# Power.net
KiCad netlist of a schematic drawn in Altium Designer
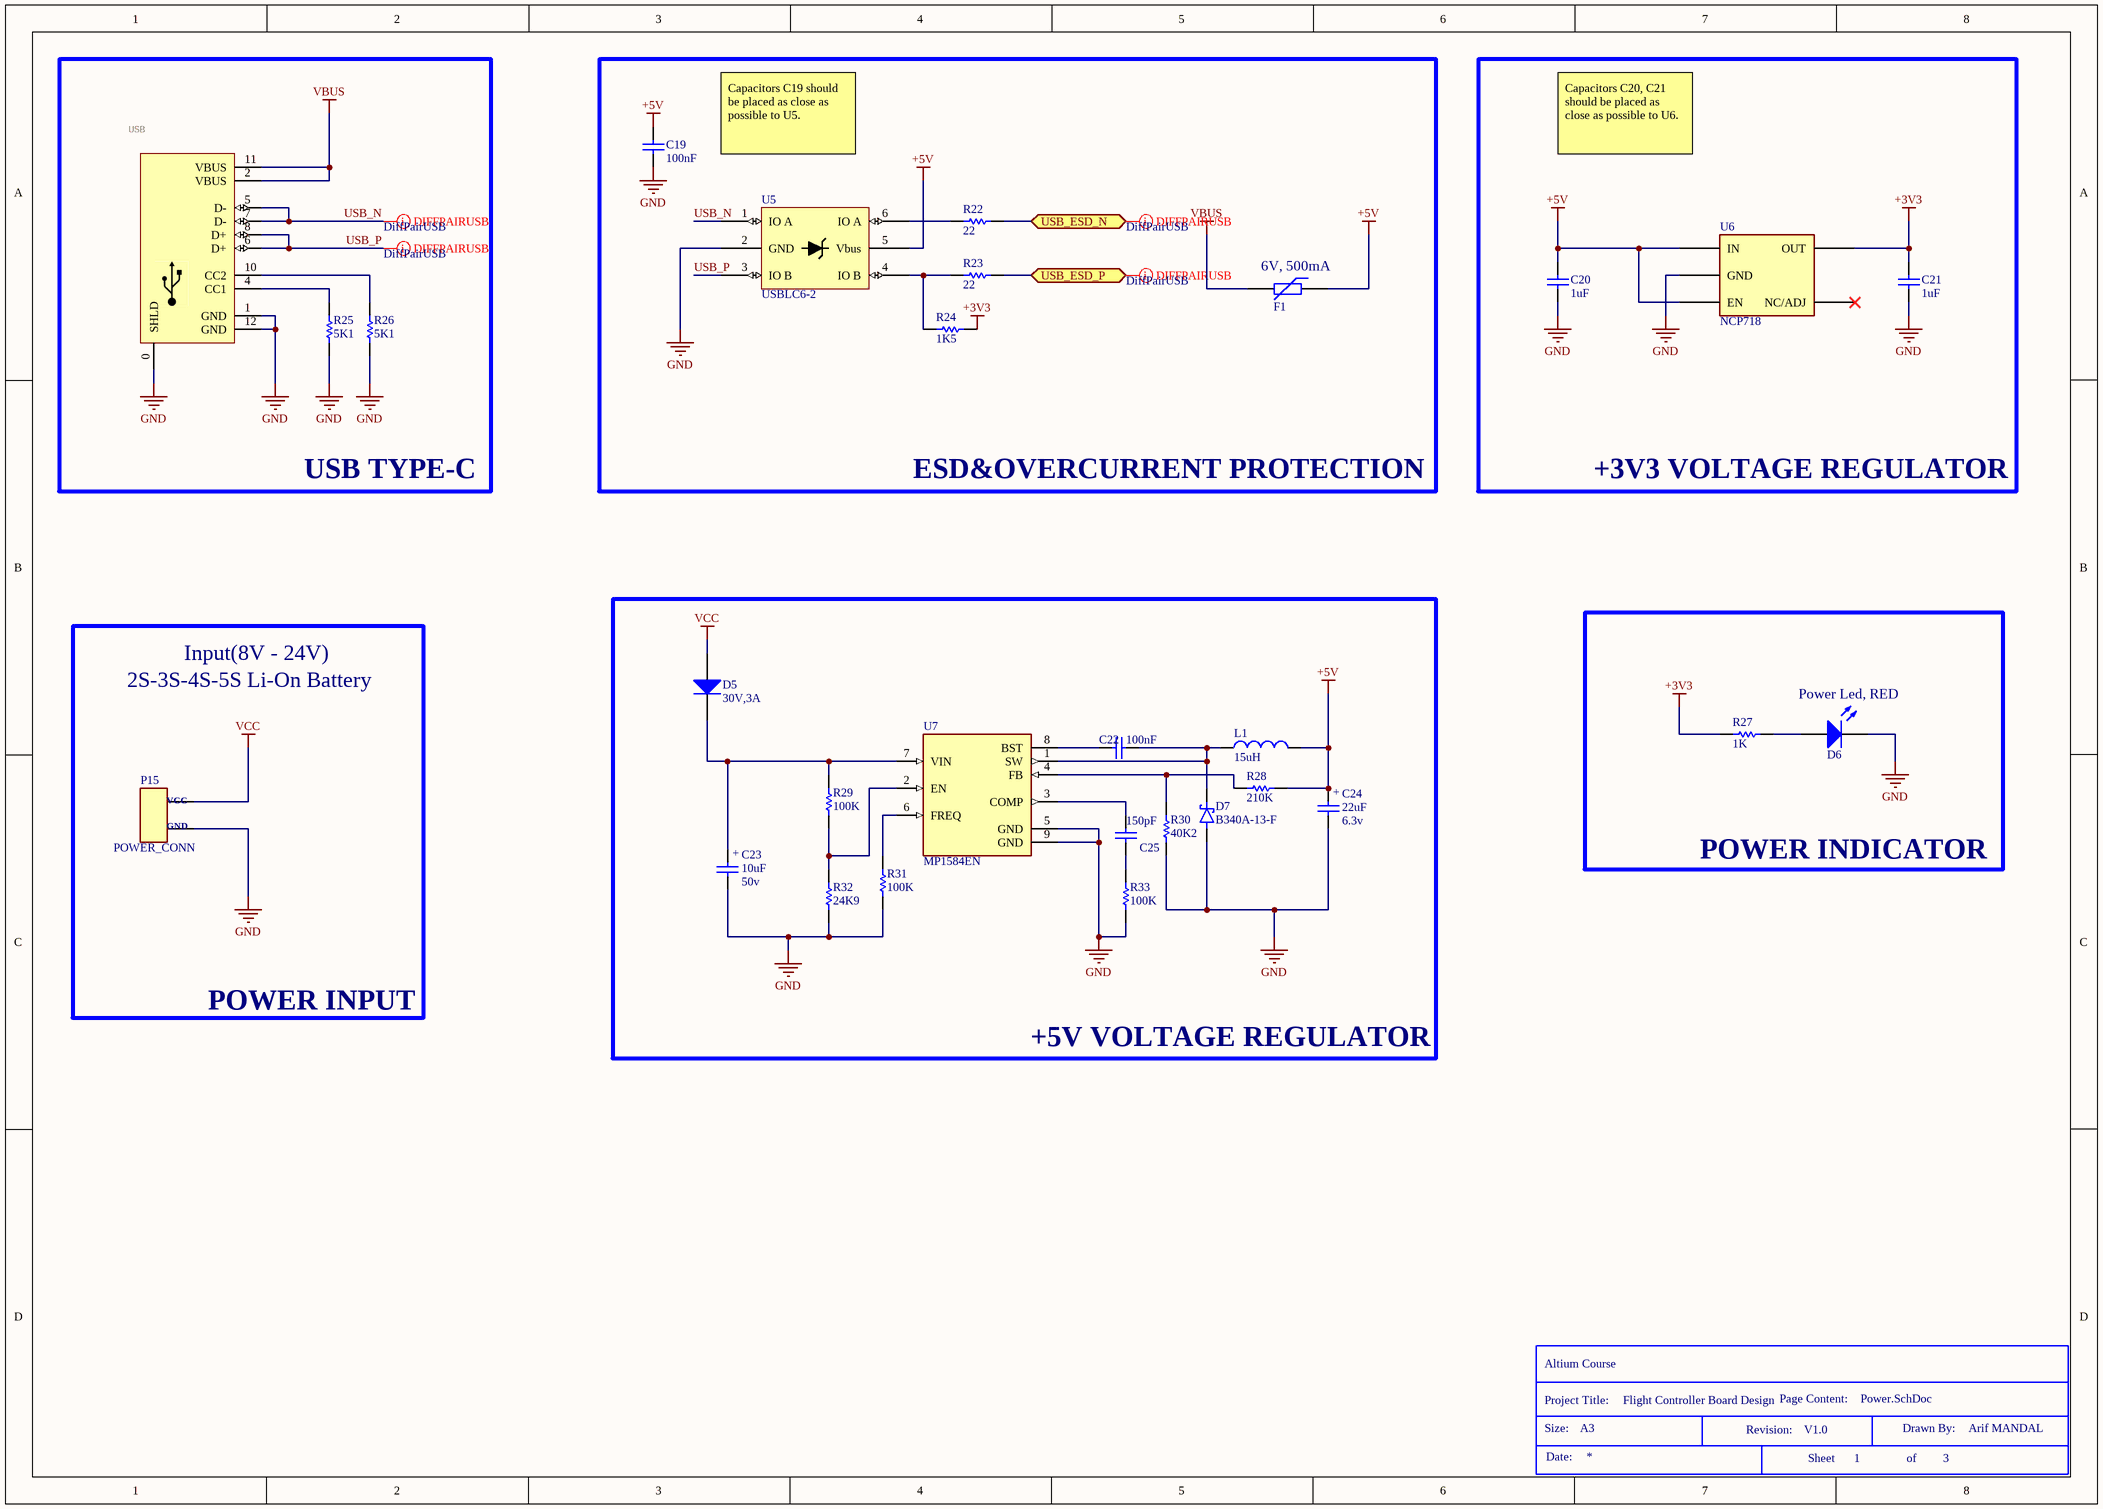
[diagram p0: Power.SchDoc]

(export (version "E")
  (design (tool "Eeschema 10.0.6"))
  (components
    (comp (ref "*")
      (value "Title Block")
      (fields (field (name "SIZE") "A3") (field (name "DRAWN BY") "Arif MANDAL"))
      (libsource (lib "Flight_Controller_Board_Design") (part "Title Block"))
    )
    (comp (ref "C19")
      (value "100nF")
      (footprint "C805")
      (description "Capacitor")
      (fields (field (name "DESIGNER") "Parsa Malekpour"))
      (libsource (lib "ParsaLibrary") (part "Cap"))
    )
    (comp (ref "C20")
      (value "1uF")
      (footprint "C805")
      (description "Capacitor")
      (fields (field (name "DESIGNER") "Parsa Malekpour"))
      (libsource (lib "ParsaLibrary") (part "Cap"))
    )
    (comp (ref "C21")
      (value "1uF")
      (footprint "C805")
      (description "Capacitor")
      (fields (field (name "DESIGNER") "Parsa Malekpour"))
      (libsource (lib "ParsaLibrary") (part "Cap"))
    )
    (comp (ref "C22")
      (value "100nF")
      (footprint "C805")
      (description "Capacitor")
      (fields (field (name "DESIGNER") "Parsa Malekpour"))
      (libsource (lib "ParsaLibrary") (part "Cap"))
    )
    (comp (ref "C23")
      (value "10uF")
      (footprint "MY_SMC_A")
      (description "Polar capacitor")
      (fields (field (name "ASID PART NUMBER") "C-AS") (field (name "VOLTE") "50v"))
      (libsource (lib "Mylib") (part "Cap Pol"))
    )
    (comp (ref "C24")
      (value "22uF")
      (footprint "MY_SMC_A")
      (description "Polar capacitor")
      (fields (field (name "ASID PART NUMBER") "C-AS") (field (name "VOLTE") "6.3v"))
      (libsource (lib "Mylib") (part "Cap Pol"))
    )
    (comp (ref "C25")
      (value "150pF")
      (footprint "C805")
      (description "Capacitor")
      (fields (field (name "DESIGNER") "Parsa Malekpour"))
      (libsource (lib "ParsaLibrary") (part "Cap"))
    )
    (comp (ref "D5")
      (value "30V,3A")
      (footprint "MY_1N4007_SMD")
      (description "1 Amp Diode")
      (fields (field (name "ASID PART NUMBER") "1n4007-AS"))
      (libsource (lib "Mylib") (part "1N4007"))
    )
    (comp (ref "D6") (value "LED") (footprint "LED-1206") (libsource (lib "ParsaLibrary") (part "LED")))
    (comp (ref "D7")
      (value "B340A-13-F")
      (footprint "DIOM5226X240N")
      (description "Diode, Rectifier, 3a, 40v, Do-214ac, Full Reel")
      (libsource (lib "Flight_Controller_Board_Design") (part "B340A-13-F"))
    )
    (comp (ref "F1")
      (value "500mA")
      (footprint "PTC-0805")
      (description "PTC")
      (libsource (lib "ParsaLibrary") (part "PTC"))
    )
    (comp (ref "L1")
      (value "15uH")
      (footprint "MY_DR73")
      (description "Inductor")
      (fields (field (name "ASID PART NUMBER") "Inductor-AS"))
      (libsource (lib "Mylib") (part "Inductor"))
    )
    (comp (ref "P15")
      (value "POWER_CONN")
      (footprint "POWER_CONN")
      (description "Li-on Battery Power Connector")
      (libsource (lib "Flight_Controller_Board_Design") (part "POWER_CONN"))
    )
    (comp (ref "R22")
      (value "22")
      (footprint "R805")
      (description "Resistor")
      (fields (field (name "DESIGNER") "Parsa Malekpour"))
      (libsource (lib "ParsaLibrary") (part "Resistor"))
    )
    (comp (ref "R23")
      (value "22")
      (footprint "R805")
      (description "Resistor")
      (fields (field (name "DESIGNER") "Parsa Malekpour"))
      (libsource (lib "ParsaLibrary") (part "Resistor"))
    )
    (comp (ref "R24")
      (value "1K5")
      (footprint "R805")
      (description "Resistor")
      (fields (field (name "DESIGNER") "Parsa Malekpour"))
      (libsource (lib "ParsaLibrary") (part "Resistor"))
    )
    (comp (ref "R25")
      (value "5K1")
      (footprint "R805")
      (description "Resistor")
      (fields (field (name "DESIGNER") "Parsa Malekpour"))
      (libsource (lib "ParsaLibrary") (part "Resistor"))
    )
    (comp (ref "R26")
      (value "5K1")
      (footprint "R805")
      (description "Resistor")
      (fields (field (name "DESIGNER") "Parsa Malekpour"))
      (libsource (lib "ParsaLibrary") (part "Resistor"))
    )
    (comp (ref "R27")
      (value "1K")
      (footprint "R805")
      (description "Resistor")
      (fields (field (name "DESIGNER") "Parsa Malekpour"))
      (libsource (lib "ParsaLibrary") (part "Resistor"))
    )
    (comp (ref "R28")
      (value "210K")
      (footprint "R805")
      (description "Resistor")
      (fields (field (name "DESIGNER") "Parsa Malekpour"))
      (libsource (lib "ParsaLibrary") (part "Resistor"))
    )
    (comp (ref "R29")
      (value "100K")
      (footprint "R805")
      (description "Resistor")
      (fields (field (name "DESIGNER") "Parsa Malekpour"))
      (libsource (lib "ParsaLibrary") (part "Resistor"))
    )
    (comp (ref "R30")
      (value "40K2")
      (footprint "R805")
      (description "Resistor")
      (fields (field (name "DESIGNER") "Parsa Malekpour"))
      (libsource (lib "ParsaLibrary") (part "Resistor"))
    )
    (comp (ref "R31")
      (value "100K")
      (footprint "R805")
      (description "Resistor")
      (fields (field (name "DESIGNER") "Parsa Malekpour"))
      (libsource (lib "ParsaLibrary") (part "Resistor"))
    )
    (comp (ref "R32")
      (value "24K9")
      (footprint "R805")
      (description "Resistor")
      (fields (field (name "DESIGNER") "Parsa Malekpour"))
      (libsource (lib "ParsaLibrary") (part "Resistor"))
    )
    (comp (ref "R33")
      (value "100K")
      (footprint "R805")
      (description "Resistor")
      (fields (field (name "DESIGNER") "Parsa Malekpour"))
      (libsource (lib "ParsaLibrary") (part "Resistor"))
    )
    (comp (ref "U5")
      (value "USBLC6-2")
      (footprint "SOT-23-6")
      (description "Very low capacitance ESD protection")
      (libsource (lib "ParsaLibrary") (part "USBLC6-2"))
    )
    (comp (ref "U6")
      (value "NCP718")
      (footprint "TSOT-23-5")
      (description "Linear Voltage Regulator IC Positive Fixed 1 Output 300mA TSOT-23-5")
      (libsource (lib "Led_Switching") (part "NCP718"))
    )
    (comp (ref "U7")
      (value "MP1584EN")
      (footprint "SOIC127P-9N")
      (fields (field (name "MF") "Monolithic Power"))
      (libsource (lib "Flight_Controller_Board_Design") (part "MP1584EN"))
    )
    (comp (ref "USB") (value "USB_C") (footprint "USB-C-5") (libsource (lib "ParsaLibrary") (part "USB_C")))
  )
  (nets
    (net (code "1") (name "+3V3") (class "Default")
      (node (ref "C21") (pin "2") (pinfunction "2_2") (pintype "passive"))
      (node (ref "R24") (pin "2") (pinfunction "2_2") (pintype "passive"))
      (node (ref "R27") (pin "1") (pinfunction "1_1") (pintype "passive"))
      (node (ref "U6") (pin "5") (pinfunction "OUT_5") (pintype "passive"))
    )
    (net (code "2") (name "+5V") (class "Default")
      (node (ref "C19") (pin "2") (pinfunction "2_2") (pintype "passive"))
      (node (ref "C20") (pin "2") (pinfunction "2_2") (pintype "passive"))
      (node (ref "C24") (pin "+") (pinfunction "+_+") (pintype "passive"))
      (node (ref "F1") (pin "1") (pinfunction "1_1") (pintype "passive"))
      (node (ref "L1") (pin "2") (pinfunction "2_2") (pintype "passive"))
      (node (ref "R28") (pin "1") (pinfunction "1_1") (pintype "passive"))
      (node (ref "U5") (pin "5") (pinfunction "Vbus_5") (pintype "power_in"))
      (node (ref "U6") (pin "1") (pinfunction "IN_1") (pintype "passive"))
      (node (ref "U6") (pin "3") (pinfunction "EN_3") (pintype "passive"))
    )
    (net (code "3") (name "/USB_ESD_N") (class "Default")
      (node (ref "R22") (pin "1") (pinfunction "1_1") (pintype "passive"))
    )
    (net (code "4") (name "/USB_ESD_P") (class "Default")
      (node (ref "R23") (pin "1") (pinfunction "1_1") (pintype "passive"))
    )
    (net (code "5") (name "/USB_N") (class "Default")
      (node (ref "U5") (pin "1") (pinfunction "IO_A_1") (pintype "bidirectional"))
      (node (ref "USB") (pin "5") (pinfunction "D-_5") (pintype "bidirectional"))
      (node (ref "USB") (pin "7") (pinfunction "D-_7") (pintype "bidirectional"))
    )
    (net (code "6") (name "/USB_P") (class "Default")
      (node (ref "U5") (pin "3") (pinfunction "IO_B_3") (pintype "bidirectional"))
      (node (ref "USB") (pin "6") (pinfunction "D+_6") (pintype "bidirectional"))
      (node (ref "USB") (pin "8") (pinfunction "D+_8") (pintype "bidirectional"))
    )
    (net (code "7") (name "GND") (class "Default")
      (node (ref "C19") (pin "1") (pinfunction "1_1") (pintype "passive"))
      (node (ref "C20") (pin "1") (pinfunction "1_1") (pintype "passive"))
      (node (ref "C21") (pin "1") (pinfunction "1_1") (pintype "passive"))
      (node (ref "C23") (pin "-") (pinfunction "-_-") (pintype "passive"))
      (node (ref "C24") (pin "-") (pinfunction "-_-") (pintype "passive"))
      (node (ref "D6") (pin "2") (pinfunction "K_2") (pintype "passive"))
      (node (ref "D7") (pin "A") (pinfunction "A_A") (pintype "passive"))
      (node (ref "P15") (pin "1") (pinfunction "GND_1") (pintype "passive"))
      (node (ref "R25") (pin "1") (pinfunction "1_1") (pintype "passive"))
      (node (ref "R26") (pin "1") (pinfunction "1_1") (pintype "passive"))
      (node (ref "R30") (pin "2") (pinfunction "2_2") (pintype "passive"))
      (node (ref "R31") (pin "1") (pinfunction "1_1") (pintype "passive"))
      (node (ref "R32") (pin "1") (pinfunction "1_1") (pintype "passive"))
      (node (ref "R33") (pin "1") (pinfunction "1_1") (pintype "passive"))
      (node (ref "U5") (pin "2") (pinfunction "GND_2") (pintype "power_in"))
      (node (ref "U6") (pin "2") (pinfunction "GND_2") (pintype "passive"))
      (node (ref "U7") (pin "5") (pinfunction "GND_5") (pintype "power_in"))
      (node (ref "U7") (pin "9") (pinfunction "GND_9") (pintype "power_in"))
      (node (ref "USB") (pin "0") (pinfunction "SHLD_0") (pintype "passive"))
      (node (ref "USB") (pin "1") (pinfunction "GND_1") (pintype "power_in"))
      (node (ref "USB") (pin "12") (pinfunction "GND_12") (pintype "power_in"))
    )
    (net (code "8") (name "Net-(C25-Pad1)") (class "Default")
      (node (ref "C25") (pin "1") (pinfunction "1_1") (pintype "passive"))
      (node (ref "R33") (pin "2") (pinfunction "2_2") (pintype "passive"))
    )
    (net (code "9") (name "Net-(D6-A)") (class "Default")
      (node (ref "D6") (pin "1") (pinfunction "A_1") (pintype "passive"))
      (node (ref "R27") (pin "2") (pinfunction "2_2") (pintype "passive"))
    )
    (net (code "10") (name "Net-(R22-Pad2)") (class "Default")
      (node (ref "R22") (pin "2") (pinfunction "2_2") (pintype "passive"))
      (node (ref "U5") (pin "6") (pinfunction "IO_A_6") (pintype "bidirectional"))
    )
    (net (code "11") (name "Net-(R23-Pad2)") (class "Default")
      (node (ref "R23") (pin "2") (pinfunction "2_2") (pintype "passive"))
      (node (ref "R24") (pin "1") (pinfunction "1_1") (pintype "passive"))
      (node (ref "U5") (pin "4") (pinfunction "IO_B_4") (pintype "bidirectional"))
    )
    (net (code "12") (name "Net-(U7-BST)") (class "Default")
      (node (ref "C22") (pin "2") (pinfunction "2_2") (pintype "passive"))
      (node (ref "U7") (pin "8") (pinfunction "BST_8") (pintype "passive"))
    )
    (net (code "13") (name "Net-(U7-COMP)") (class "Default")
      (node (ref "C25") (pin "2") (pinfunction "2_2") (pintype "passive"))
      (node (ref "U7") (pin "3") (pinfunction "COMP_3") (pintype "output"))
    )
    (net (code "14") (name "Net-(U7-EN)") (class "Default")
      (node (ref "R29") (pin "1") (pinfunction "1_1") (pintype "passive"))
      (node (ref "R32") (pin "2") (pinfunction "2_2") (pintype "passive"))
      (node (ref "U7") (pin "2") (pinfunction "EN_2") (pintype "input"))
    )
    (net (code "15") (name "Net-(U7-FB)") (class "Default")
      (node (ref "R28") (pin "2") (pinfunction "2_2") (pintype "passive"))
      (node (ref "R30") (pin "1") (pinfunction "1_1") (pintype "passive"))
      (node (ref "U7") (pin "4") (pinfunction "FB_4") (pintype "input"))
    )
    (net (code "16") (name "Net-(U7-FREQ)") (class "Default")
      (node (ref "R31") (pin "2") (pinfunction "2_2") (pintype "passive"))
      (node (ref "U7") (pin "6") (pinfunction "FREQ_6") (pintype "input"))
    )
    (net (code "17") (name "Net-(U7-SW)") (class "Default")
      (node (ref "C22") (pin "1") (pinfunction "1_1") (pintype "passive"))
      (node (ref "D7") (pin "C") (pinfunction "C_C") (pintype "passive"))
      (node (ref "L1") (pin "1") (pinfunction "1_1") (pintype "passive"))
      (node (ref "U7") (pin "1") (pinfunction "SW_1") (pintype "output"))
    )
    (net (code "18") (name "Net-(U7-VIN)") (class "Default")
      (node (ref "C23") (pin "+") (pinfunction "+_+") (pintype "passive"))
      (node (ref "D5") (pin "K") (pinfunction "K_K") (pintype "passive"))
      (node (ref "R29") (pin "2") (pinfunction "2_2") (pintype "passive"))
      (node (ref "U7") (pin "7") (pinfunction "VIN_7") (pintype "input"))
    )
    (net (code "19") (name "Net-(USB-CC1)") (class "Default")
      (node (ref "R25") (pin "2") (pinfunction "2_2") (pintype "passive"))
      (node (ref "USB") (pin "4") (pinfunction "CC1_4") (pintype "passive"))
    )
    (net (code "20") (name "Net-(USB-CC2)") (class "Default")
      (node (ref "R26") (pin "2") (pinfunction "2_2") (pintype "passive"))
      (node (ref "USB") (pin "10") (pinfunction "CC2_10") (pintype "passive"))
    )
    (net (code "21") (name "VBUS") (class "Default")
      (node (ref "F1") (pin "2") (pinfunction "2_2") (pintype "passive"))
      (node (ref "USB") (pin "11") (pinfunction "VBUS_11") (pintype "power_in"))
      (node (ref "USB") (pin "2") (pinfunction "VBUS_2") (pintype "power_in"))
    )
    (net (code "22") (name "VCC") (class "Default")
      (node (ref "D5") (pin "A") (pinfunction "A_A") (pintype "passive"))
      (node (ref "P15") (pin "0") (pinfunction "VCC_0") (pintype "passive"))
    )
    (net (code "23") (name "unconnected-(U6-NC{slash}ADJ-Pad4)") (class "Default")
      (node (ref "U6") (pin "4") (pinfunction "NC/ADJ_4") (pintype "passive+no_connect"))
    )
  )
)
